# Sheet1.net
KiCad netlist of a schematic drawn in Altium Designer
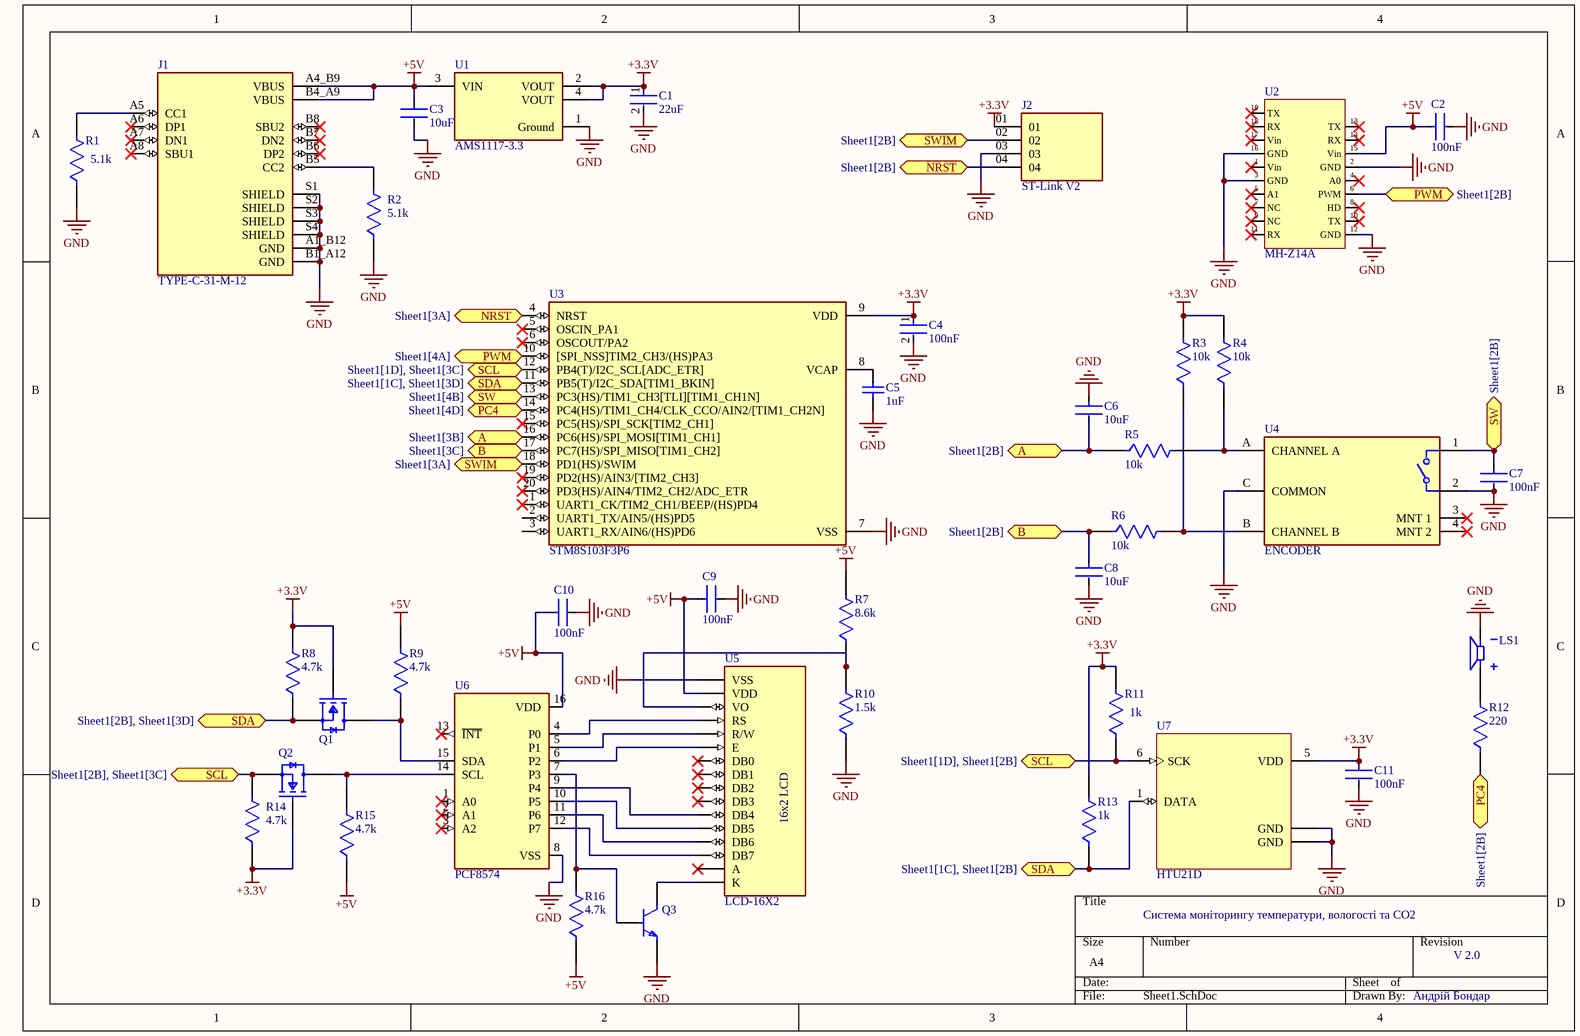
[diagram p0: Sheet1.SchDoc]

(export (version "E")
  (design (tool "Eeschema 10.0.6"))
  (components
    (comp (ref "C1")
      (value "22uF")
      (footprint "FP-CGA5L-0_3-0_1-MFG")
      (description "Cap Ceramic 22uF 6.3V X7R 20% Pad SMD 1206 +125°C Automotive T/R")
      (fields (field (name "TOLERANCE") "20%"))
      (libsource (lib "Altium Content Vault") (part "b4654b650e69147ec39a6b967a45e02"))
    )
    (comp (ref "C2")
      (value "100nF")
      (footprint "FP-AC1206-0_85-MFG")
      (description "CAP CER 0.1UF 100V X7R 1206")
      (fields
        (field (name "OCTOPART") "https://octopart.com/ac1206kkx7r0bb104-yageo-75666120")
        (field (name "TOLERANCE") "0.1")
      )
      (libsource (lib "Altium Content Vault") (part "11868f565c42a9108669ba33697ecf6"))
    )
    (comp (ref "C3")
      (value "10uF")
      (footprint "FP-C3216-160-0_2-IPC_B")
      (description "Multilayer Ceramic Capacitors 10uF ±20% 25V X7R SMD 1206")
      (fields (field (name "TOLERANCE") "20%"))
      (libsource (lib "Altium Content Vault") (part "11868f565c42a9108669ba33697ecf6"))
    )
    (comp (ref "C4")
      (value "100nF")
      (footprint "FP-AC1206-0_85-MFG")
      (description "CAP CER 0.1UF 100V X7R 1206")
      (fields
        (field (name "OCTOPART") "https://octopart.com/ac1206kkx7r0bb104-yageo-75666120")
        (field (name "TOLERANCE") "0.1")
      )
      (libsource (lib "") (part "11868f565c42a9108669ba33697ecf6_1"))
    )
    (comp (ref "C5")
      (value "1uF")
      (footprint "CAPC1206(3216)150_L")
      (description "CAP 1uF 16V ±20% 1206 (3216 Metric) Thickness 1.45mm SMD")
      (fields (field (name "TOLERANCE") "Â±20%"))
      (libsource (lib "Altium Content Vault") (part "CAP"))
    )
    (comp (ref "C6")
      (value "10uF")
      (footprint "FP-C3216-160-0_2-IPC_B")
      (description "Multilayer Ceramic Capacitors 10uF ±20% 25V X7R SMD 1206")
      (fields (field (name "TOLERANCE") "20%"))
      (libsource (lib "Altium Content Vault") (part "11868f565c42a9108669ba33697ecf6"))
    )
    (comp (ref "C7")
      (value "100nF")
      (footprint "FP-AC1206-0_85-MFG")
      (description "CAP CER 0.1UF 100V X7R 1206")
      (fields
        (field (name "OCTOPART") "https://octopart.com/ac1206kkx7r0bb104-yageo-75666120")
        (field (name "TOLERANCE") "0.1")
      )
      (libsource (lib "Altium Content Vault") (part "11868f565c42a9108669ba33697ecf6"))
    )
    (comp (ref "C8")
      (value "10uF")
      (footprint "FP-C3216-160-0_2-IPC_B")
      (description "Multilayer Ceramic Capacitors 10uF ±20% 25V X7R SMD 1206")
      (fields (field (name "TOLERANCE") "20%"))
      (libsource (lib "Altium Content Vault") (part "11868f565c42a9108669ba33697ecf6"))
    )
    (comp (ref "C9")
      (value "100nF")
      (footprint "FP-AC1206-0_85-MFG")
      (description "CAP CER 0.1UF 100V X7R 1206")
      (fields
        (field (name "OCTOPART") "https://octopart.com/ac1206kkx7r0bb104-yageo-75666120")
        (field (name "TOLERANCE") "0.1")
      )
      (libsource (lib "Altium Content Vault") (part "11868f565c42a9108669ba33697ecf6"))
    )
    (comp (ref "C10")
      (value "100nF")
      (footprint "FP-AC1206-0_85-MFG")
      (description "CAP CER 0.1UF 100V X7R 1206")
      (fields
        (field (name "OCTOPART") "https://octopart.com/ac1206kkx7r0bb104-yageo-75666120")
        (field (name "TOLERANCE") "0.1")
      )
      (libsource (lib "Altium Content Vault") (part "11868f565c42a9108669ba33697ecf6"))
    )
    (comp (ref "C11")
      (value "100nF")
      (footprint "FP-AC1206-0_85-MFG")
      (description "CAP CER 0.1UF 100V X7R 1206")
      (fields
        (field (name "OCTOPART") "https://octopart.com/ac1206kkx7r0bb104-yageo-75666120")
        (field (name "TOLERANCE") "0.1")
      )
      (libsource (lib "Altium Content Vault") (part "11868f565c42a9108669ba33697ecf6"))
    )
    (comp (ref "J1")
      (value "TYPE-C-31-M-12")
      (footprint "HRO_TYPE-C-31-M-12")
      (description "USB Connectors 24 Receptacle 1 8.94*7.3mm RoHS")
      (fields (field (name "MF") "HRO Electronics Co., Ltd."))
      (libsource (lib "TYPE-C-31-M-12") (part "TYPE-C-31-M-12"))
    )
    (comp (ref "J2")
      (value "ST-Link V2")
      (footprint "SAMTEC_MTSW-104-07-G-S-200")
      (fields (field (name "MP") "MTSW-104-07-G-S-200"))
      (libsource (lib "MTSW-104-07-G-S-200") (part "MTSW-104-07-G-S-200"))
    )
    (comp (ref "LS1")
      (value "CPI-148-24-90T-67")
      (footprint "XDCR_CPI-148-24-90T-67")
      (fields (field (name "MF") "Same Sky"))
      (libsource (lib "CPI-148-24-90T-67") (part "CPI-148-24-90T-67"))
    )
    (comp (ref "Q1")
      (value "BSS138")
      (footprint "FP-318-08-IPC_B")
      (description "MOSFET N-CH 50V 220MA SOT-23")
      (libsource (lib "Altium Content Vault") (part "3b9c635fedb024a5347a57b145af9cc"))
    )
    (comp (ref "Q2")
      (value "BSS138")
      (footprint "FP-318-08-IPC_B")
      (description "MOSFET N-CH 50V 220MA SOT-23")
      (libsource (lib "Altium Content Vault") (part "3b9c635fedb024a5347a57b145af9cc"))
    )
    (comp (ref "Q3")
      (value "SS8050DBU")
      (footprint "FP-135AN-MFG")
      (description "SS8050DBU Bipolar (BJT) Single Transistor, NPN, 25 V, 100 MHz, 1 W, 1.5 A, 160")
      (libsource (lib "Altium Content Vault") (part "a64cbfbad643015290886283bc510aa"))
    )
    (comp (ref "R1")
      (value "5.1k")
      (footprint "FP-ESR18-IPC_A")
      (description "5.1kΩ ±1% 0.5W 1206 Anti-Surge Chip Resistor AEC-Q200")
      (fields (field (name "TOLERANCE") "1%"))
      (libsource (lib "Altium Content Vault") (part "1029c3af85768c4190bb7ad29bc67b5"))
    )
    (comp (ref "R2")
      (value "5.1k")
      (footprint "FP-ESR18-IPC_A")
      (description "5.1kΩ ±1% 0.5W 1206 Anti-Surge Chip Resistor AEC-Q200")
      (fields (field (name "TOLERANCE") "1%"))
      (libsource (lib "Altium Content Vault") (part "1029c3af85768c4190bb7ad29bc67b5"))
    )
    (comp (ref "R3")
      (value "10k")
      (footprint "FP-SR1206-MFG")
      (description "RES 10K OHM 1% 1/2W 1206")
      (fields
        (field (name "MANUFACTURER PART NUMBER") "SR1206FR-7W10KL")
        (field (name "OCTOPART") "https://octopart.com/sr1206fr-7w10kl-yageo-92673874")
      )
      (libsource (lib "Altium Content Vault") (part "1029c3af85768c4190bb7ad29bc67b5"))
    )
    (comp (ref "R4")
      (value "10k")
      (footprint "FP-SR1206-MFG")
      (description "RES 10K OHM 1% 1/2W 1206")
      (fields
        (field (name "MANUFACTURER PART NUMBER") "SR1206FR-7W10KL")
        (field (name "OCTOPART") "https://octopart.com/sr1206fr-7w10kl-yageo-92673874")
      )
      (libsource (lib "Altium Content Vault") (part "1029c3af85768c4190bb7ad29bc67b5"))
    )
    (comp (ref "R5")
      (value "10k")
      (footprint "FP-SR1206-MFG")
      (description "RES 10K OHM 1% 1/2W 1206")
      (fields
        (field (name "MANUFACTURER PART NUMBER") "SR1206FR-7W10KL")
        (field (name "OCTOPART") "https://octopart.com/sr1206fr-7w10kl-yageo-92673874")
      )
      (libsource (lib "Altium Content Vault") (part "1029c3af85768c4190bb7ad29bc67b5"))
    )
    (comp (ref "R6")
      (value "10k")
      (footprint "FP-SR1206-MFG")
      (description "RES 10K OHM 1% 1/2W 1206")
      (fields
        (field (name "MANUFACTURER PART NUMBER") "SR1206FR-7W10KL")
        (field (name "OCTOPART") "https://octopart.com/sr1206fr-7w10kl-yageo-92673874")
      )
      (libsource (lib "Altium Content Vault") (part "1029c3af85768c4190bb7ad29bc67b5"))
    )
    (comp (ref "R7")
      (value "8.6k")
      (footprint "FP-RP732B-MFG")
      (description "Res Thin Film 1206 8.66KΩ 0.1% 0.25W 15ppm/°C Molded SMD")
      (fields (field (name "MANUFACTURER") "TE Connectivity") (field (name "TOLERANCE") "0.1%"))
      (libsource (lib "Altium Content Vault") (part "1029c3af85768c4190bb7ad29bc67b5"))
    )
    (comp (ref "R8")
      (value "4.7k")
      (footprint "FP-CRCW1206-Pe3-IPC_A")
      (description "RES Thick Film, 4.7kΩ, 1%, 0.25W, 50ppm/°C, 1206")
      (fields (field (name "TOLERANCE") "1%"))
      (libsource (lib "Altium Content Vault") (part "1029c3af85768c4190bb7ad29bc67b5"))
    )
    (comp (ref "R9")
      (value "4.7k")
      (footprint "FP-CRCW1206-Pe3-IPC_A")
      (description "RES Thick Film, 4.7kΩ, 1%, 0.25W, 50ppm/°C, 1206")
      (fields (field (name "TOLERANCE") "1%"))
      (libsource (lib "Altium Content Vault") (part "1029c3af85768c4190bb7ad29bc67b5"))
    )
    (comp (ref "R10")
      (value "1.5k")
      (footprint "FP-RMCF1206-MFG")
      (description "1.5kΩ ±1% 0.25W 1206 Thick Film Chip Resistor AEC-Q200 compliant")
      (fields (field (name "TOLERANCE") "1%"))
      (libsource (lib "Altium Content Vault") (part "1029c3af85768c4190bb7ad29bc67b5"))
    )
    (comp (ref "R11")
      (value "1k")
      (footprint "FP-RMCF1206-IPC_A")
      (description "1kΩ ±5% 0.25W 1206 Thick Film Chip Resistor AEC-Q200 compliant")
      (fields (field (name "TOLERANCE") "5%"))
      (libsource (lib "Altium Content Vault") (part "1029c3af85768c4190bb7ad29bc67b5"))
    )
    (comp (ref "R12")
      (value "220")
      (footprint "FP-SR1206-MFG")
      (description "RES SMD 220 OHM 1% 1/2W 1206")
      (fields
        (field (name "OCTOPART") "https://octopart.com/sr1206fr-7w220rl-yageo-71414967")
        (field (name "MANUFACTURER PART NUMBER") "SR1206FR-7W220RL")
      )
      (libsource (lib "Altium Content Vault") (part "1029c3af85768c4190bb7ad29bc67b5"))
    )
    (comp (ref "R13")
      (value "1k")
      (footprint "FP-RMCF1206-IPC_A")
      (description "1kΩ ±5% 0.25W 1206 Thick Film Chip Resistor AEC-Q200 compliant")
      (fields (field (name "TOLERANCE") "5%"))
      (libsource (lib "Altium Content Vault") (part "1029c3af85768c4190bb7ad29bc67b5"))
    )
    (comp (ref "R14")
      (value "4.7k")
      (footprint "FP-CRCW1206-Pe3-IPC_A")
      (description "RES Thick Film, 4.7kΩ, 1%, 0.25W, 50ppm/°C, 1206")
      (fields (field (name "TOLERANCE") "1%"))
      (libsource (lib "Altium Content Vault") (part "1029c3af85768c4190bb7ad29bc67b5"))
    )
    (comp (ref "R15")
      (value "4.7k")
      (footprint "FP-CRCW1206-Pe3-IPC_A")
      (description "RES Thick Film, 4.7kΩ, 1%, 0.25W, 50ppm/°C, 1206")
      (fields (field (name "TOLERANCE") "1%"))
      (libsource (lib "Altium Content Vault") (part "1029c3af85768c4190bb7ad29bc67b5"))
    )
    (comp (ref "R16")
      (value "4.7k")
      (footprint "FP-CRCW1206-Pe3-IPC_A")
      (description "RES Thick Film, 4.7kΩ, 1%, 0.25W, 50ppm/°C, 1206")
      (fields (field (name "TOLERANCE") "1%"))
      (libsource (lib "Altium Content Vault") (part "1029c3af85768c4190bb7ad29bc67b5"))
    )
    (comp (ref "U1")
      (value "AMS1117-3.3")
      (footprint "FP-AMS1117-IPC_C")
      (description "LDO Voltage Regulators 1A, 3.3V")
      (fields
        (field (name "OCTOPART") "https://octopart.com/ams1117-3.3-advanced+monolithic+systems-25899300")
        (field (name "MANUFACTURER") "Advanced Monolithic Systems")
      )
      (libsource (lib "Altium Content Vault") (part "8bdbb5f8e77002000e30dd2845d0354"))
    )
    (comp (ref "U2") (value "MH-Z14A") (footprint "MH-Z14A") (libsource (lib "Schlib1") (part "MH-Z14A")))
    (comp (ref "U3")
      (value "STM8S103F3P6")
      (footprint "SOP65P640X120-20N")
      (description "STM8 series Microcontroller IC 8-Bit 16MHz 8KB (8K x 8) FLASH 20-TSSOP")
      (fields (field (name "MF") "STMicroelectronics"))
      (libsource (lib "STM8S103F3P6 (1)") (part "STM8S103F3P6"))
    )
    (comp (ref "U4")
      (value "ENCODER")
      (footprint "FP-PEC11R-4115F-S0018-MFG")
      (description "ROTARY ENCODER MECHANICAL 18PPR")
      (libsource (lib "Altium Content Vault") (part "61735aed983a166c614e16033f3d545"))
    )
    (comp (ref "U5")
      (value "LCD-16X2")
      (footprint "MODULE_LCD-16X2")
      (description "Display Development Tools 16x2 Black on Green Char LCD w Backlight")
      (fields (field (name "MF") "Gravitech"))
      (libsource (lib "LCD-16X2") (part "LCD-16X2"))
    )
    (comp (ref "U6")
      (value "PCF8574")
      (footprint "SOP65P640X150-20N")
      (description "I/O Expander 8 IÂ²C 100 kHz 20-VQFN (3.5x4.5)")
      (fields (field (name "MF") "Texas Instruments"))
      (libsource (lib "PCF8574") (part "PCF8574"))
    )
    (comp (ref "U7")
      (value "HTU21D")
      (footprint "QFN100P300X300X100-7N")
      (description "Humidity Temperature Sensor 0 ~ 100% RH IÂ²C Â±2% RH 5s Surface Mount")
      (fields (field (name "MF") "TE Connectivity"))
      (libsource (lib "SnapEDAsch") (part "HTU21D"))
    )
  )
  (nets
    (net (code "1") (name "+3.3V") (class "Default")
      (node (ref "C1") (pin "1") (pinfunction "1_1") (pintype "passive"))
      (node (ref "C11") (pin "1") (pinfunction "1_1") (pintype "passive"))
      (node (ref "C4") (pin "1") (pinfunction "1_1") (pintype "passive"))
      (node (ref "J2") (pin "01") (pinfunction "01_01") (pintype "passive"))
      (node (ref "Q1") (pin "1") (pinfunction "G_1") (pintype "passive"))
      (node (ref "Q2") (pin "1") (pinfunction "G_1") (pintype "passive"))
      (node (ref "R11") (pin "2") (pinfunction "2_2") (pintype "passive"))
      (node (ref "R13") (pin "2") (pinfunction "2_2") (pintype "passive"))
      (node (ref "R14") (pin "1") (pinfunction "1_1") (pintype "passive"))
      (node (ref "R3") (pin "2") (pinfunction "2_2") (pintype "passive"))
      (node (ref "R4") (pin "2") (pinfunction "2_2") (pintype "passive"))
      (node (ref "R8") (pin "2") (pinfunction "2_2") (pintype "passive"))
      (node (ref "U1") (pin "2") (pinfunction "VOUT_2") (pintype "passive"))
      (node (ref "U1") (pin "4") (pinfunction "VOUT_4") (pintype "passive"))
      (node (ref "U3") (pin "9") (pinfunction "VDD_9") (pintype "power_in"))
      (node (ref "U7") (pin "5") (pinfunction "VDD_5") (pintype "power_in"))
    )
    (net (code "2") (name "+5V") (class "Default")
      (node (ref "C10") (pin "1") (pinfunction "1_1") (pintype "passive"))
      (node (ref "C2") (pin "1") (pinfunction "1_1") (pintype "passive"))
      (node (ref "C3") (pin "1") (pinfunction "1_1") (pintype "passive"))
      (node (ref "C9") (pin "1") (pinfunction "1_1") (pintype "passive"))
      (node (ref "J1") (pin "A4_B9") (pinfunction "VBUS_A4_B9") (pintype "power_in"))
      (node (ref "J1") (pin "B4_A9") (pinfunction "VBUS_B4_A9") (pintype "power_in"))
      (node (ref "R15") (pin "1") (pinfunction "1_1") (pintype "passive"))
      (node (ref "R16") (pin "1") (pinfunction "1_1") (pintype "passive"))
      (node (ref "R7") (pin "2") (pinfunction "2_2") (pintype "passive"))
      (node (ref "R9") (pin "2") (pinfunction "2_2") (pintype "passive"))
      (node (ref "U1") (pin "3") (pinfunction "VIN_3") (pintype "power_in"))
      (node (ref "U2") (pin "15") (pinfunction "Vin_15") (pintype "passive"))
      (node (ref "U5") (pin "2") (pinfunction "VDD_2") (pintype "power_in"))
      (node (ref "U6") (pin "16") (pinfunction "VDD_16") (pintype "power_in"))
    )
    (net (code "3") (name "/A") (class "Default")
      (node (ref "C6") (pin "2") (pinfunction "2_2") (pintype "passive"))
      (node (ref "R5") (pin "1") (pinfunction "1_1") (pintype "passive"))
      (node (ref "U3") (pin "16") (pinfunction "PC6(HS)/SPI_MOSI[TIM1_CH1]_16") (pintype "bidirectional"))
    )
    (net (code "4") (name "/B") (class "Default")
      (node (ref "C8") (pin "1") (pinfunction "1_1") (pintype "passive"))
      (node (ref "R6") (pin "1") (pinfunction "1_1") (pintype "passive"))
      (node (ref "U3") (pin "17") (pinfunction "PC7(HS)/SPI_MISO[TIM1_CH2]_17") (pintype "bidirectional"))
    )
    (net (code "5") (name "/NRST") (class "Default")
      (node (ref "J2") (pin "04") (pinfunction "04_04") (pintype "passive"))
      (node (ref "U3") (pin "4") (pinfunction "NRST_4") (pintype "bidirectional"))
    )
    (net (code "6") (name "/PC4") (class "Default")
      (node (ref "R12") (pin "1") (pinfunction "1_1") (pintype "passive"))
      (node (ref "U3") (pin "14") (pinfunction "PC4(HS)/TIM1_CH4/CLK_CCO/AIN2/[TIM1_CH2N]_14") (pintype "bidirectional"))
    )
    (net (code "7") (name "/PWM") (class "Default")
      (node (ref "U2") (pin "6") (pinfunction "PWM_6") (pintype "passive"))
      (node (ref "U3") (pin "10") (pinfunction "[SPI_NSS]TIM2_CH3/(HS)PA3_10") (pintype "bidirectional"))
    )
    (net (code "8") (name "/SCL") (class "Default")
      (node (ref "Q2") (pin "2") (pinfunction "S_2") (pintype "passive"))
      (node (ref "R11") (pin "1") (pinfunction "1_1") (pintype "passive"))
      (node (ref "R14") (pin "2") (pinfunction "2_2") (pintype "passive"))
      (node (ref "U3") (pin "12") (pinfunction "PB4(T)/I2C_SCL[ADC_ETR]_12") (pintype "bidirectional"))
      (node (ref "U7") (pin "6") (pinfunction "SCK_6") (pintype "input"))
    )
    (net (code "9") (name "/SDA") (class "Default")
      (node (ref "Q1") (pin "2") (pinfunction "S_2") (pintype "passive"))
      (node (ref "R13") (pin "1") (pinfunction "1_1") (pintype "passive"))
      (node (ref "R8") (pin "1") (pinfunction "1_1") (pintype "passive"))
      (node (ref "U3") (pin "11") (pinfunction "PB5(T)/I2C_SDA[TIM1_BKIN]_11") (pintype "bidirectional"))
      (node (ref "U7") (pin "1") (pinfunction "DATA_1") (pintype "bidirectional"))
    )
    (net (code "10") (name "/SW") (class "Default")
      (node (ref "C7") (pin "1") (pinfunction "1_1") (pintype "passive"))
      (node (ref "U3") (pin "13") (pinfunction "PC3(HS)/TIM1_CH3[TLI][TIM1_CH1N]_13") (pintype "bidirectional"))
      (node (ref "U4") (pin "1") (pinfunction "1_1") (pintype "passive"))
    )
    (net (code "11") (name "/SWIM") (class "Default")
      (node (ref "J2") (pin "02") (pinfunction "02_02") (pintype "passive"))
      (node (ref "U3") (pin "18") (pinfunction "PD1(HS)/SWIM_18") (pintype "bidirectional"))
    )
    (net (code "12") (name "GND") (class "Default")
      (node (ref "C1") (pin "2") (pinfunction "2_2") (pintype "passive"))
      (node (ref "C10") (pin "2") (pinfunction "2_2") (pintype "passive"))
      (node (ref "C11") (pin "2") (pinfunction "2_2") (pintype "passive"))
      (node (ref "C2") (pin "2") (pinfunction "2_2") (pintype "passive"))
      (node (ref "C3") (pin "2") (pinfunction "2_2") (pintype "passive"))
      (node (ref "C4") (pin "2") (pinfunction "2_2") (pintype "passive"))
      (node (ref "C5") (pin "1") (pinfunction "1_1") (pintype "passive"))
      (node (ref "C6") (pin "1") (pinfunction "1_1") (pintype "passive"))
      (node (ref "C7") (pin "2") (pinfunction "2_2") (pintype "passive"))
      (node (ref "C8") (pin "2") (pinfunction "2_2") (pintype "passive"))
      (node (ref "C9") (pin "2") (pinfunction "2_2") (pintype "passive"))
      (node (ref "J1") (pin "A1_B12") (pinfunction "GND_A1_B12") (pintype "power_in"))
      (node (ref "J1") (pin "B1_A12") (pinfunction "GND_B1_A12") (pintype "power_in"))
      (node (ref "J1") (pin "S1") (pinfunction "SHIELD_S1") (pintype "passive"))
      (node (ref "J1") (pin "S2") (pinfunction "SHIELD_S2") (pintype "passive"))
      (node (ref "J1") (pin "S3") (pinfunction "SHIELD_S3") (pintype "passive"))
      (node (ref "J1") (pin "S4") (pinfunction "SHIELD_S4") (pintype "passive"))
      (node (ref "J2") (pin "03") (pinfunction "03_03") (pintype "passive"))
      (node (ref "LS1") (pin "N") (pinfunction "N_N") (pintype "passive"))
      (node (ref "Q3") (pin "1") (pinfunction "E_1") (pintype "passive"))
      (node (ref "R1") (pin "1") (pinfunction "1_1") (pintype "passive"))
      (node (ref "R10") (pin "1") (pinfunction "1_1") (pintype "passive"))
      (node (ref "R2") (pin "1") (pinfunction "1_1") (pintype "passive"))
      (node (ref "U1") (pin "1") (pinfunction "Ground_1") (pintype "power_in"))
      (node (ref "U2") (pin "12") (pinfunction "GND_12") (pintype "passive"))
      (node (ref "U2") (pin "16") (pinfunction "GND_16") (pintype "passive"))
      (node (ref "U2") (pin "2") (pinfunction "GND_2") (pintype "passive"))
      (node (ref "U2") (pin "3") (pinfunction "GND_3") (pintype "passive"))
      (node (ref "U3") (pin "7") (pinfunction "VSS_7") (pintype "power_in"))
      (node (ref "U4") (pin "2") (pinfunction "2_2") (pintype "passive"))
      (node (ref "U4") (pin "C") (pinfunction "COMMON_C") (pintype "passive"))
      (node (ref "U5") (pin "1") (pinfunction "VSS_1") (pintype "power_in"))
      (node (ref "U6") (pin "8") (pinfunction "VSS_8") (pintype "power_in"))
      (node (ref "U7") (pin "2") (pinfunction "GND_2") (pintype "passive"))
      (node (ref "U7") (pin "PAD") (pinfunction "GND_PAD") (pintype "passive"))
    )
    (net (code "13") (name "Net-(J1-CC1)") (class "Default")
      (node (ref "J1") (pin "A5") (pinfunction "CC1_A5") (pintype "bidirectional"))
      (node (ref "R1") (pin "2") (pinfunction "2_2") (pintype "passive"))
    )
    (net (code "14") (name "Net-(J1-CC2)") (class "Default")
      (node (ref "J1") (pin "B5") (pinfunction "CC2_B5") (pintype "bidirectional"))
      (node (ref "R2") (pin "2") (pinfunction "2_2") (pintype "passive"))
    )
    (net (code "15") (name "Net-(LS1-PadP)") (class "Default")
      (node (ref "LS1") (pin "P") (pinfunction "P_P") (pintype "passive"))
      (node (ref "R12") (pin "2") (pinfunction "2_2") (pintype "passive"))
    )
    (net (code "16") (name "Net-(Q1-D)") (class "Default")
      (node (ref "Q1") (pin "3") (pinfunction "D_3") (pintype "passive"))
      (node (ref "R9") (pin "1") (pinfunction "1_1") (pintype "passive"))
      (node (ref "U6") (pin "15") (pinfunction "SDA_15") (pintype "bidirectional"))
    )
    (net (code "17") (name "Net-(Q2-D)") (class "Default")
      (node (ref "Q2") (pin "3") (pinfunction "D_3") (pintype "passive"))
      (node (ref "R15") (pin "2") (pinfunction "2_2") (pintype "passive"))
      (node (ref "U6") (pin "14") (pinfunction "SCL_14") (pintype "bidirectional"))
    )
    (net (code "18") (name "Net-(Q3-B)") (class "Default")
      (node (ref "Q3") (pin "2") (pinfunction "B_2") (pintype "passive"))
      (node (ref "R16") (pin "2") (pinfunction "2_2") (pintype "passive"))
      (node (ref "U6") (pin "7") (pinfunction "P3_7") (pintype "bidirectional"))
    )
    (net (code "19") (name "Net-(Q3-C)") (class "Default")
      (node (ref "Q3") (pin "3") (pinfunction "C_3") (pintype "passive"))
      (node (ref "U5") (pin "16") (pinfunction "K_16") (pintype "power_in"))
    )
    (net (code "20") (name "Net-(U3-VCAP)") (class "Default")
      (node (ref "C5") (pin "2") (pinfunction "2_2") (pintype "passive"))
      (node (ref "U3") (pin "8") (pinfunction "VCAP_8") (pintype "passive"))
    )
    (net (code "21") (name "Net-(U4-CHANNEL_A)") (class "Default")
      (node (ref "R4") (pin "1") (pinfunction "1_1") (pintype "passive"))
      (node (ref "R5") (pin "2") (pinfunction "2_2") (pintype "passive"))
      (node (ref "U4") (pin "A") (pinfunction "CHANNEL_A_A") (pintype "passive"))
    )
    (net (code "22") (name "Net-(U4-CHANNEL_B)") (class "Default")
      (node (ref "R3") (pin "1") (pinfunction "1_1") (pintype "passive"))
      (node (ref "R6") (pin "2") (pinfunction "2_2") (pintype "passive"))
      (node (ref "U4") (pin "B") (pinfunction "CHANNEL_B_B") (pintype "passive"))
    )
    (net (code "23") (name "Net-(U5-DB4)") (class "Default")
      (node (ref "U5") (pin "11") (pinfunction "DB4_11") (pintype "bidirectional"))
      (node (ref "U6") (pin "9") (pinfunction "P4_9") (pintype "bidirectional"))
    )
    (net (code "24") (name "Net-(U5-DB5)") (class "Default")
      (node (ref "U5") (pin "12") (pinfunction "DB5_12") (pintype "bidirectional"))
      (node (ref "U6") (pin "10") (pinfunction "P5_10") (pintype "bidirectional"))
    )
    (net (code "25") (name "Net-(U5-DB6)") (class "Default")
      (node (ref "U5") (pin "13") (pinfunction "DB6_13") (pintype "bidirectional"))
      (node (ref "U6") (pin "11") (pinfunction "P6_11") (pintype "bidirectional"))
    )
    (net (code "26") (name "Net-(U5-DB7)") (class "Default")
      (node (ref "U5") (pin "14") (pinfunction "DB7_14") (pintype "bidirectional"))
      (node (ref "U6") (pin "12") (pinfunction "P7_12") (pintype "bidirectional"))
    )
    (net (code "27") (name "Net-(U5-E)") (class "Default")
      (node (ref "U5") (pin "6") (pinfunction "E_6") (pintype "input"))
      (node (ref "U6") (pin "6") (pinfunction "P2_6") (pintype "bidirectional"))
    )
    (net (code "28") (name "Net-(U5-RS)") (class "Default")
      (node (ref "U5") (pin "4") (pinfunction "RS_4") (pintype "input"))
      (node (ref "U6") (pin "4") (pinfunction "P0_4") (pintype "bidirectional"))
    )
    (net (code "29") (name "Net-(U5-R{slash}W)") (class "Default")
      (node (ref "U5") (pin "5") (pinfunction "R/W_5") (pintype "input"))
      (node (ref "U6") (pin "5") (pinfunction "P1_5") (pintype "bidirectional"))
    )
    (net (code "30") (name "Net-(U5-VO)") (class "Default")
      (node (ref "R10") (pin "2") (pinfunction "2_2") (pintype "passive"))
      (node (ref "R7") (pin "1") (pinfunction "1_1") (pintype "passive"))
      (node (ref "U5") (pin "3") (pinfunction "VO_3") (pintype "bidirectional"))
    )
    (net (code "31") (name "unconnected-(J1-DN1-PadA7)") (class "Default")
      (node (ref "J1") (pin "A7") (pinfunction "DN1_A7") (pintype "bidirectional+no_connect"))
    )
    (net (code "32") (name "unconnected-(J1-DN2-PadB7)") (class "Default")
      (node (ref "J1") (pin "B7") (pinfunction "DN2_B7") (pintype "bidirectional+no_connect"))
    )
    (net (code "33") (name "unconnected-(J1-DP1-PadA6)") (class "Default")
      (node (ref "J1") (pin "A6") (pinfunction "DP1_A6") (pintype "bidirectional+no_connect"))
    )
    (net (code "34") (name "unconnected-(J1-DP2-PadB6)") (class "Default")
      (node (ref "J1") (pin "B6") (pinfunction "DP2_B6") (pintype "bidirectional+no_connect"))
    )
    (net (code "35") (name "unconnected-(J1-SBU1-PadA8)") (class "Default")
      (node (ref "J1") (pin "A8") (pinfunction "SBU1_A8") (pintype "bidirectional+no_connect"))
    )
    (net (code "36") (name "unconnected-(J1-SBU2-PadB8)") (class "Default")
      (node (ref "J1") (pin "B8") (pinfunction "SBU2_B8") (pintype "bidirectional+no_connect"))
    )
    (net (code "37") (name "unconnected-(U2-A0-Pad4)") (class "Default")
      (node (ref "U2") (pin "4") (pinfunction "A0_4") (pintype "passive+no_connect"))
    )
    (net (code "38") (name "unconnected-(U2-A1-Pad5)") (class "Default")
      (node (ref "U2") (pin "5") (pinfunction "A1_5") (pintype "passive+no_connect"))
    )
    (net (code "39") (name "unconnected-(U2-HD-Pad8)") (class "Default")
      (node (ref "U2") (pin "8") (pinfunction "HD_8") (pintype "passive+no_connect"))
    )
    (net (code "40") (name "unconnected-(U2-NC-Pad7)") (class "Default")
      (node (ref "U2") (pin "7") (pinfunction "NC_7") (pintype "passive+no_connect"))
    )
    (net (code "41") (name "unconnected-(U2-NC-Pad9)") (class "Default")
      (node (ref "U2") (pin "9") (pinfunction "NC_9") (pintype "passive+no_connect"))
    )
    (net (code "42") (name "unconnected-(U2-RX-Pad11)") (class "Default")
      (node (ref "U2") (pin "11") (pinfunction "RX_11") (pintype "passive+no_connect"))
    )
    (net (code "43") (name "unconnected-(U2-RX-Pad14)") (class "Default")
      (node (ref "U2") (pin "14") (pinfunction "RX_14") (pintype "passive+no_connect"))
    )
    (net (code "44") (name "unconnected-(U2-RX-Pad18)") (class "Default")
      (node (ref "U2") (pin "18") (pinfunction "RX_18") (pintype "passive+no_connect"))
    )
    (net (code "45") (name "unconnected-(U2-TX-Pad10)") (class "Default")
      (node (ref "U2") (pin "10") (pinfunction "TX_10") (pintype "passive+no_connect"))
    )
    (net (code "46") (name "unconnected-(U2-TX-Pad13)") (class "Default")
      (node (ref "U2") (pin "13") (pinfunction "TX_13") (pintype "passive+no_connect"))
    )
    (net (code "47") (name "unconnected-(U2-TX-Pad19)") (class "Default")
      (node (ref "U2") (pin "19") (pinfunction "TX_19") (pintype "passive+no_connect"))
    )
    (net (code "48") (name "unconnected-(U2-Vin-Pad1)") (class "Default")
      (node (ref "U2") (pin "1") (pinfunction "Vin_1") (pintype "passive+no_connect"))
    )
    (net (code "49") (name "unconnected-(U2-Vin-Pad17)") (class "Default")
      (node (ref "U2") (pin "17") (pinfunction "Vin_17") (pintype "passive+no_connect"))
    )
    (net (code "50") (name "unconnected-(U3-OSCIN_PA1-Pad5)") (class "Default")
      (node (ref "U3") (pin "5") (pinfunction "OSCIN_PA1_5") (pintype "bidirectional+no_connect"))
    )
    (net (code "51") (name "unconnected-(U3-OSCOUT{slash}PA2-Pad6)") (class "Default")
      (node (ref "U3") (pin "6") (pinfunction "OSCOUT/PA2_6") (pintype "bidirectional+no_connect"))
    )
    (net (code "52") (name "unconnected-(U3-PC5(HS){slash}SPI_SCK[TIM2_CH1]-Pad15)") (class "Default")
      (node (ref "U3") (pin "15") (pinfunction "PC5(HS)/SPI_SCK[TIM2_CH1]_15") (pintype "bidirectional+no_connect"))
    )
    (net (code "53") (name "unconnected-(U3-PD2(HS){slash}AIN3{slash}[TIM2_CH3]-Pad19)") (class "Default")
      (node (ref "U3") (pin "19") (pinfunction "PD2(HS)/AIN3/[TIM2_CH3]_19") (pintype "bidirectional+no_connect"))
    )
    (net (code "54") (name "unconnected-(U3-PD3(HS){slash}AIN4{slash}TIM2_CH2{slash}ADC_ETR-Pad20)") (class "Default")
      (node (ref "U3") (pin "20") (pinfunction "PD3(HS)/AIN4/TIM2_CH2/ADC_ETR_20") (pintype "bidirectional+no_connect"))
    )
    (net (code "55") (name "unconnected-(U3-UART1_CK{slash}TIM2_CH1{slash}BEEP{slash}(HS)PD4-Pad1)") (class "Default")
      (node (ref "U3") (pin "1") (pinfunction "UART1_CK/TIM2_CH1/BEEP/(HS)PD4_1") (pintype "bidirectional+no_connect"))
    )
    (net (code "56") (name "unconnected-(U3-UART1_RX{slash}AIN6{slash}(HS)PD6-Pad3)") (class "Default")
      (node (ref "U3") (pin "3") (pinfunction "UART1_RX/AIN6/(HS)PD6_3") (pintype "bidirectional"))
    )
    (net (code "57") (name "unconnected-(U3-UART1_TX{slash}AIN5{slash}(HS)PD5-Pad2)") (class "Default")
      (node (ref "U3") (pin "2") (pinfunction "UART1_TX/AIN5/(HS)PD5_2") (pintype "bidirectional"))
    )
    (net (code "58") (name "unconnected-(U4-MNT_1-Pad3)") (class "Default")
      (node (ref "U4") (pin "3") (pinfunction "MNT_1_3") (pintype "passive+no_connect"))
    )
    (net (code "59") (name "unconnected-(U4-MNT_2-Pad4)") (class "Default")
      (node (ref "U4") (pin "4") (pinfunction "MNT_2_4") (pintype "passive+no_connect"))
    )
    (net (code "60") (name "unconnected-(U5-A-Pad15)") (class "Default")
      (node (ref "U5") (pin "15") (pinfunction "A_15") (pintype "power_in+no_connect"))
    )
    (net (code "61") (name "unconnected-(U5-DB0-Pad7)") (class "Default")
      (node (ref "U5") (pin "7") (pinfunction "DB0_7") (pintype "bidirectional+no_connect"))
    )
    (net (code "62") (name "unconnected-(U5-DB1-Pad8)") (class "Default")
      (node (ref "U5") (pin "8") (pinfunction "DB1_8") (pintype "bidirectional+no_connect"))
    )
    (net (code "63") (name "unconnected-(U5-DB2-Pad9)") (class "Default")
      (node (ref "U5") (pin "9") (pinfunction "DB2_9") (pintype "bidirectional+no_connect"))
    )
    (net (code "64") (name "unconnected-(U5-DB3-Pad10)") (class "Default")
      (node (ref "U5") (pin "10") (pinfunction "DB3_10") (pintype "bidirectional+no_connect"))
    )
    (net (code "65") (name "unconnected-(U6-A0-Pad1)") (class "Default")
      (node (ref "U6") (pin "1") (pinfunction "A0_1") (pintype "input+no_connect"))
    )
    (net (code "66") (name "unconnected-(U6-A1-Pad2)") (class "Default")
      (node (ref "U6") (pin "2") (pinfunction "A1_2") (pintype "input+no_connect"))
    )
    (net (code "67") (name "unconnected-(U6-A2-Pad3)") (class "Default")
      (node (ref "U6") (pin "3") (pinfunction "A2_3") (pintype "input+no_connect"))
    )
    (net (code "68") (name "unconnected-(U6-~{INT}-Pad13)") (class "Default")
      (node (ref "U6") (pin "13") (pinfunction "~{INT}_13") (pintype "output+no_connect"))
    )
  )
)
